# PG02_Full_Bridge.net
KiCad netlist of a schematic drawn in Altium Designer
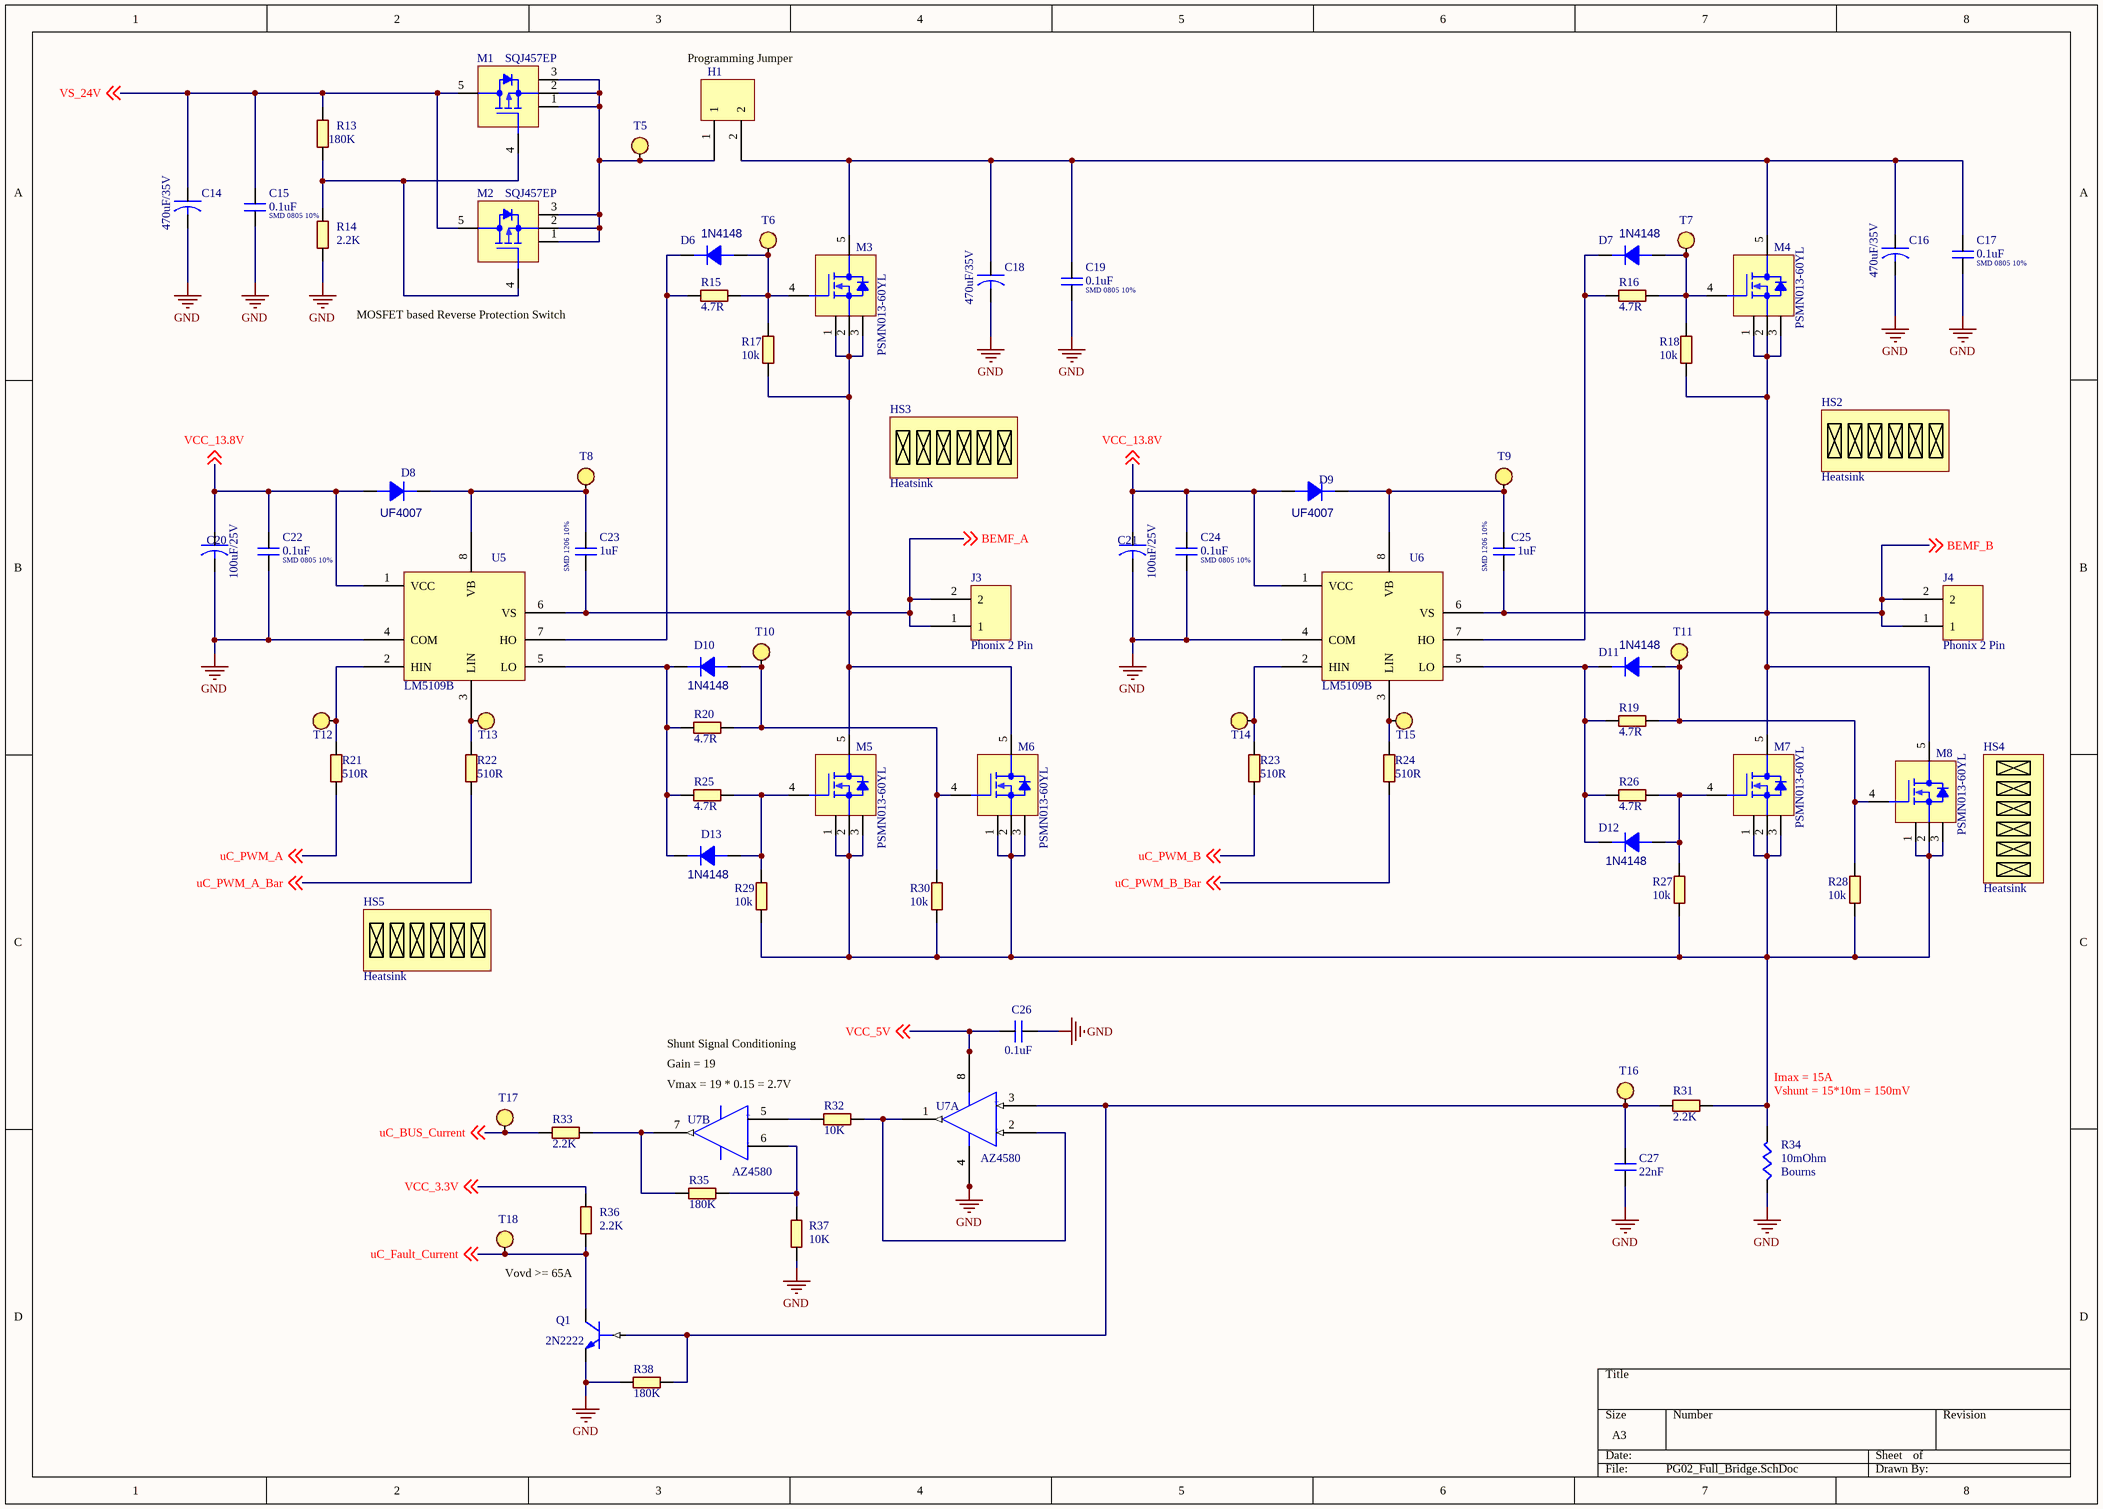
[diagram p0: PG02_Full_Bridge.SchDoc]

(export (version "E")
  (design (tool "Eeschema 10.0.6"))
  (components
    (comp (ref "C14")
      (value "470uF/35V")
      (fields (field (name "Comment") "Electrolyte Cap"))
      (libsource (lib "*") (part "CAP"))
    )
    (comp (ref "C15")
      (value "SMD 0805 10%")
      (footprint "SMD0805")
      (fields (field (name "MANUFACTURER") "Vishay") (field (name "ALTIUM_VALUE") "0.1uF"))
      (libsource (lib "Schlib1") (part "CAP_SMD"))
    )
    (comp (ref "C16")
      (value "470uF/35V")
      (fields (field (name "Comment") "Electrolyte Cap"))
      (libsource (lib "*") (part "CAP"))
    )
    (comp (ref "C17")
      (value "SMD 0805 10%")
      (footprint "SMD0805")
      (fields (field (name "MANUFACTURER") "Vishay") (field (name "ALTIUM_VALUE") "0.1uF"))
      (libsource (lib "Schlib1") (part "CAP_SMD"))
    )
    (comp (ref "C18")
      (value "470uF/35V")
      (fields (field (name "Comment") "Electrolyte Cap"))
      (libsource (lib "*") (part "CAP"))
    )
    (comp (ref "C19")
      (value "SMD 0805 10%")
      (footprint "SMD0805")
      (fields (field (name "MANUFACTURER") "Vishay") (field (name "ALTIUM_VALUE") "0.1uF"))
      (libsource (lib "Schlib1") (part "CAP_SMD"))
    )
    (comp (ref "C20") (value "100uF/25V") (footprint "CAP 5MM") (libsource (lib "*") (part "CAP")))
    (comp (ref "C21") (value "100uF/25V") (footprint "CAP 5MM") (libsource (lib "*") (part "CAP")))
    (comp (ref "C22")
      (value "SMD 0805 10%")
      (footprint "SMD0805")
      (fields (field (name "MANUFACTURER") "Vishay") (field (name "ALTIUM_VALUE") "0.1uF"))
      (libsource (lib "Schlib1") (part "CAP_SMD"))
    )
    (comp (ref "C23")
      (value "SMD 1206 10%")
      (footprint "SMD1206")
      (fields (field (name "MANUFACTURER") "Vishay") (field (name "ALTIUM_VALUE") "1uF"))
      (libsource (lib "Schlib1") (part "CAP_SMD"))
    )
    (comp (ref "C24")
      (value "SMD 0805 10%")
      (footprint "SMD0805")
      (fields (field (name "MANUFACTURER") "Vishay") (field (name "ALTIUM_VALUE") "0.1uF"))
      (libsource (lib "Schlib1") (part "CAP_SMD"))
    )
    (comp (ref "C25")
      (value "SMD 1206 10%")
      (footprint "SMD1206")
      (fields (field (name "MANUFACTURER") "Vishay") (field (name "ALTIUM_VALUE") "1uF"))
      (libsource (lib "Schlib1") (part "CAP_SMD"))
    )
    (comp (ref "C26")
      (value "0.1uF")
      (footprint "SMD0805")
      (fields (field (name "MANUFACTURER") "Vishay") (field (name "Comment") "SMD 0805 10%"))
      (libsource (lib "Schlib1") (part "CAP_SMD"))
    )
    (comp (ref "C27")
      (value "22nF")
      (footprint "SMD0805")
      (fields (field (name "MANUFACTURER") "Vishay") (field (name "Comment") "SMD 0805 10%"))
      (libsource (lib "Schlib1") (part "CAP_SMD"))
    )
    (comp (ref "D6")
      (value "1N4148")
      (fields
        (field (name "PART NO.") "SM4007")
        (field (name "TOLERANCE") "10%")
        (field (name "MANUFACTURER") "Vishay")
      )
      (libsource (lib "*") (part "1N4148"))
    )
    (comp (ref "D7")
      (value "1N4148")
      (fields
        (field (name "PART NO.") "SM4007")
        (field (name "TOLERANCE") "10%")
        (field (name "MANUFACTURER") "Vishay")
      )
      (libsource (lib "*") (part "1N4148"))
    )
    (comp (ref "D8")
      (value "UF4007")
      (fields
        (field (name "PART NO.") "SM4007")
        (field (name "TOLERANCE") "10%")
        (field (name "MANUFACTURER") "Vishay")
      )
      (libsource (lib "*") (part "1N4148"))
    )
    (comp (ref "D9")
      (value "UF4007")
      (fields
        (field (name "PART NO.") "SM4007")
        (field (name "TOLERANCE") "10%")
        (field (name "MANUFACTURER") "Vishay")
      )
      (libsource (lib "*") (part "1N4148"))
    )
    (comp (ref "D10")
      (value "1N4148")
      (fields
        (field (name "PART NO.") "SM4007")
        (field (name "TOLERANCE") "10%")
        (field (name "MANUFACTURER") "Vishay")
      )
      (libsource (lib "*") (part "1N4148"))
    )
    (comp (ref "D11")
      (value "1N4148")
      (fields
        (field (name "PART NO.") "SM4007")
        (field (name "TOLERANCE") "10%")
        (field (name "MANUFACTURER") "Vishay")
      )
      (libsource (lib "*") (part "1N4148"))
    )
    (comp (ref "D12")
      (value "1N4148")
      (fields
        (field (name "PART NO.") "SM4007")
        (field (name "TOLERANCE") "10%")
        (field (name "MANUFACTURER") "Vishay")
      )
      (libsource (lib "*") (part "1N4148"))
    )
    (comp (ref "D13")
      (value "1N4148")
      (fields
        (field (name "PART NO.") "SM4007")
        (field (name "TOLERANCE") "10%")
        (field (name "MANUFACTURER") "Vishay")
      )
      (libsource (lib "*") (part "1N4148"))
    )
    (comp (ref "H1")
      (value "Header 2 pin")
      (footprint "Header-2-Pin")
      (libsource (lib "Schlib1") (part "Header_2_Pin"))
    )
    (comp (ref "HS2") (value "Heatsink") (footprint "Heatsink_25mm") (libsource (lib "") (part "HS_15W_1")))
    (comp (ref "HS3") (value "Heatsink") (footprint "Heatsink_25mm") (libsource (lib "") (part "HS_15W_1")))
    (comp (ref "HS4")
      (value "Heatsink")
      (footprint "Heatsink_25mm")
      (libsource (lib "Schlib1") (part "HS_15W"))
    )
    (comp (ref "HS5") (value "Heatsink") (footprint "Heatsink_25mm") (libsource (lib "") (part "HS_15W_1")))
    (comp (ref "J3")
      (value "Phonix 2 Pin")
      (footprint "PHONIX2")
      (libsource (lib "Schlib1") (part "Phonix_2_Pin"))
    )
    (comp (ref "J4")
      (value "Phonix 2 Pin")
      (footprint "PHONIX2")
      (libsource (lib "Schlib1") (part "Phonix_2_Pin"))
    )
    (comp (ref "M1")
      (value "SQJ457EP")
      (footprint "SO8-L")
      (fields (field (name "MANUFACTURER") "Vishay") (field (name "Comment") "P MOSFET"))
      (libsource (lib "Schlib1") (part "PMOS_SQJ457EP"))
    )
    (comp (ref "M2")
      (value "SQJ457EP")
      (footprint "SO8-L")
      (fields (field (name "MANUFACTURER") "Vishay") (field (name "Comment") "P MOSFET"))
      (libsource (lib "Schlib1") (part "PMOS_SQJ457EP"))
    )
    (comp (ref "M3")
      (value "PSMN013-60YL")
      (footprint "SO8-L")
      (fields (field (name "MANUFACTURER") "NxP") (field (name "Comment") "N MOSFET"))
      (libsource (lib "Schlib1") (part "MOS_PSMN013-60YL"))
    )
    (comp (ref "M4")
      (value "PSMN013-60YL")
      (footprint "SO8-L")
      (fields (field (name "MANUFACTURER") "NxP") (field (name "Comment") "N MOSFET"))
      (libsource (lib "Schlib1") (part "MOS_PSMN013-60YL"))
    )
    (comp (ref "M5")
      (value "PSMN013-60YL")
      (footprint "SO8-L")
      (fields (field (name "MANUFACTURER") "NxP") (field (name "Comment") "N MOSFET"))
      (libsource (lib "Schlib1") (part "MOS_PSMN013-60YL"))
    )
    (comp (ref "M6")
      (value "PSMN013-60YL")
      (footprint "SO8-L")
      (fields (field (name "MANUFACTURER") "NxP") (field (name "Comment") "N MOSFET"))
      (libsource (lib "Schlib1") (part "MOS_PSMN013-60YL"))
    )
    (comp (ref "M7")
      (value "PSMN013-60YL")
      (footprint "SO8-L")
      (fields (field (name "MANUFACTURER") "NxP") (field (name "Comment") "N MOSFET"))
      (libsource (lib "Schlib1") (part "MOS_PSMN013-60YL"))
    )
    (comp (ref "M8")
      (value "PSMN013-60YL")
      (footprint "SO8-L")
      (fields (field (name "MANUFACTURER") "NxP") (field (name "Comment") "N MOSFET"))
      (libsource (lib "Schlib1") (part "MOS_PSMN013-60YL"))
    )
    (comp (ref "Q1")
      (value "2N2222")
      (fields (field (name "MANUFACTURER") "OnSemi") (field (name "Comment") "NPN Transistor"))
      (libsource (lib "*") (part "2N3904_1"))
    )
    (comp (ref "R13")
      (value "180K")
      (footprint "SMD1206")
      (description "SMD1206  1% Resistor")
      (fields (field (name "MANUFACTURER") "Vishay") (field (name "Comment") "SMD 1206 1%"))
      (libsource (lib "") (part "RES_SMD_1"))
    )
    (comp (ref "R14")
      (value "2.2K")
      (footprint "SMD1206")
      (description "SMD1206  1% Resistor")
      (fields (field (name "MANUFACTURER") "Vishay") (field (name "Comment") "SMD 1206 1%"))
      (libsource (lib "") (part "RES_SMD_1"))
    )
    (comp (ref "R15")
      (value "4.7R")
      (footprint "SMD1206")
      (description "SMD1206  1% Resistor")
      (fields (field (name "MANUFACTURER") "Vishay") (field (name "Comment") "SMD 1206 1%"))
      (libsource (lib "") (part "RES_SMD_2"))
    )
    (comp (ref "R16")
      (value "4.7R")
      (footprint "SMD1206")
      (description "SMD1206  1% Resistor")
      (fields (field (name "MANUFACTURER") "Vishay") (field (name "Comment") "SMD 1206 1%"))
      (libsource (lib "") (part "RES_SMD_2"))
    )
    (comp (ref "R17")
      (value "10k")
      (footprint "SMD1206")
      (description "SMD1206  1% Resistor")
      (fields (field (name "MANUFACTURER") "Vishay") (field (name "Comment") "SMD 1206 1%"))
      (libsource (lib "") (part "RES_SMD_3"))
    )
    (comp (ref "R18")
      (value "10k")
      (footprint "SMD1206")
      (description "SMD1206  1% Resistor")
      (fields (field (name "MANUFACTURER") "Vishay") (field (name "Comment") "SMD 1206 1%"))
      (libsource (lib "") (part "RES_SMD_3"))
    )
    (comp (ref "R19")
      (value "4.7R")
      (footprint "SMD1206")
      (description "SMD1206  1% Resistor")
      (fields (field (name "MANUFACTURER") "Vishay") (field (name "Comment") "SMD 1206 1%"))
      (libsource (lib "") (part "RES_SMD_2"))
    )
    (comp (ref "R20")
      (value "4.7R")
      (footprint "SMD1206")
      (description "SMD1206  1% Resistor")
      (fields (field (name "MANUFACTURER") "Vishay") (field (name "Comment") "SMD 1206 1%"))
      (libsource (lib "Schlib1") (part "RES_SMD"))
    )
    (comp (ref "R21")
      (value "510R")
      (footprint "SMD1206")
      (description "SMD1206  1% Resistor")
      (fields (field (name "MANUFACTURER") "Vishay") (field (name "Comment") "SMD 1206 1%"))
      (libsource (lib "") (part "RES_SMD_1"))
    )
    (comp (ref "R22")
      (value "510R")
      (footprint "SMD1206")
      (description "SMD1206  1% Resistor")
      (fields (field (name "MANUFACTURER") "Vishay") (field (name "Comment") "SMD 1206 1%"))
      (libsource (lib "") (part "RES_SMD_1"))
    )
    (comp (ref "R23")
      (value "510R")
      (footprint "SMD1206")
      (description "SMD1206  1% Resistor")
      (fields (field (name "MANUFACTURER") "Vishay") (field (name "Comment") "SMD 1206 1%"))
      (libsource (lib "") (part "RES_SMD_1"))
    )
    (comp (ref "R24")
      (value "510R")
      (footprint "SMD1206")
      (description "SMD1206  1% Resistor")
      (fields (field (name "MANUFACTURER") "Vishay") (field (name "Comment") "SMD 1206 1%"))
      (libsource (lib "") (part "RES_SMD_1"))
    )
    (comp (ref "R25")
      (value "4.7R")
      (footprint "SMD1206")
      (description "SMD1206  1% Resistor")
      (fields (field (name "MANUFACTURER") "Vishay") (field (name "Comment") "SMD 1206 1%"))
      (libsource (lib "") (part "RES_SMD_2"))
    )
    (comp (ref "R26")
      (value "4.7R")
      (footprint "SMD1206")
      (description "SMD1206  1% Resistor")
      (fields (field (name "MANUFACTURER") "Vishay") (field (name "Comment") "SMD 1206 1%"))
      (libsource (lib "") (part "RES_SMD_2"))
    )
    (comp (ref "R27")
      (value "10k")
      (footprint "SMD1206")
      (description "SMD1206  1% Resistor")
      (fields (field (name "MANUFACTURER") "Vishay") (field (name "Comment") "SMD 1206 1%"))
      (libsource (lib "") (part "RES_SMD_3"))
    )
    (comp (ref "R28")
      (value "10k")
      (footprint "SMD1206")
      (description "SMD1206  1% Resistor")
      (fields (field (name "MANUFACTURER") "Vishay") (field (name "Comment") "SMD 1206 1%"))
      (libsource (lib "") (part "RES_SMD_3"))
    )
    (comp (ref "R29")
      (value "10k")
      (footprint "SMD1206")
      (description "SMD1206  1% Resistor")
      (fields (field (name "MANUFACTURER") "Vishay") (field (name "Comment") "SMD 1206 1%"))
      (libsource (lib "") (part "RES_SMD_3"))
    )
    (comp (ref "R30")
      (value "10k")
      (footprint "SMD1206")
      (description "SMD1206  1% Resistor")
      (fields (field (name "MANUFACTURER") "Vishay") (field (name "Comment") "SMD 1206 1%"))
      (libsource (lib "") (part "RES_SMD_3"))
    )
    (comp (ref "R31")
      (value "2.2K")
      (footprint "SMD1206")
      (description "SMD1206  1% Resistor")
      (fields (field (name "MANUFACTURER") "Vishay") (field (name "Comment") "SMD 1206 1%"))
      (libsource (lib "Schlib1") (part "RES_SMD"))
    )
    (comp (ref "R32")
      (value "10K")
      (footprint "SMD1206")
      (description "SMD1206  1% Resistor")
      (fields (field (name "MANUFACTURER") "Vishay") (field (name "Comment") "SMD 1206 1%"))
      (libsource (lib "Schlib1") (part "RES_SMD"))
    )
    (comp (ref "R33")
      (value "2.2K")
      (footprint "SMD1206")
      (description "SMD1206  1% Resistor")
      (fields (field (name "MANUFACTURER") "Vishay") (field (name "Comment") "SMD 1206 1%"))
      (libsource (lib "Schlib1") (part "RES_SMD"))
    )
    (comp (ref "R34")
      (value "10mOhm")
      (footprint "SMD2512")
      (fields (field (name "MANUFACTURER") "Bourns") (field (name "Comment") "CRA2512"))
      (libsource (lib "Schlib1") (part "RES_TH"))
    )
    (comp (ref "R35")
      (value "180K")
      (footprint "SMD1206")
      (description "SMD1206  1% Resistor")
      (fields (field (name "MANUFACTURER") "Vishay") (field (name "Comment") "SMD 1206 1%"))
      (libsource (lib "Schlib1") (part "RES_SMD"))
    )
    (comp (ref "R36")
      (value "2.2K")
      (footprint "SMD1206")
      (description "SMD1206  1% Resistor")
      (fields (field (name "MANUFACTURER") "Vishay") (field (name "Comment") "SMD 1206 1%"))
      (libsource (lib "") (part "RES_SMD_3"))
    )
    (comp (ref "R37")
      (value "10K")
      (footprint "SMD1206")
      (description "SMD1206  1% Resistor")
      (fields (field (name "MANUFACTURER") "Vishay") (field (name "Comment") "SMD 1206 1%"))
      (libsource (lib "") (part "RES_SMD_3"))
    )
    (comp (ref "R38")
      (value "180K")
      (footprint "SMD1206")
      (description "SMD1206  1% Resistor")
      (fields (field (name "MANUFACTURER") "Vishay") (field (name "Comment") "SMD 1206 1%"))
      (libsource (lib "Schlib1") (part "RES_SMD"))
    )
    (comp (ref "T5")
      (value "Through hole TestPoint")
      (footprint "TP")
      (libsource (lib "Schlib1") (part "TestPoint_TH"))
    )
    (comp (ref "T6")
      (value "Through hole TestPoint")
      (footprint "TP")
      (libsource (lib "Schlib1") (part "TestPoint_TH"))
    )
    (comp (ref "T7")
      (value "Through hole TestPoint")
      (footprint "TP")
      (libsource (lib "Schlib1") (part "TestPoint_TH"))
    )
    (comp (ref "T8")
      (value "Through hole TestPoint")
      (footprint "TP")
      (libsource (lib "Schlib1") (part "TestPoint_TH"))
    )
    (comp (ref "T9")
      (value "Through hole TestPoint")
      (footprint "TP")
      (libsource (lib "Schlib1") (part "TestPoint_TH"))
    )
    (comp (ref "T10")
      (value "Through hole TestPoint")
      (footprint "TP")
      (libsource (lib "Schlib1") (part "TestPoint_TH"))
    )
    (comp (ref "T11")
      (value "Through hole TestPoint")
      (footprint "TP")
      (libsource (lib "Schlib1") (part "TestPoint_TH"))
    )
    (comp (ref "T12")
      (value "Through hole TestPoint")
      (footprint "TP")
      (libsource (lib "") (part "TestPoint_TH_2"))
    )
    (comp (ref "T13")
      (value "Through hole TestPoint")
      (footprint "TP")
      (libsource (lib "") (part "TestPoint_TH_1"))
    )
    (comp (ref "T14")
      (value "Through hole TestPoint")
      (footprint "TP")
      (libsource (lib "") (part "TestPoint_TH_2"))
    )
    (comp (ref "T15")
      (value "Through hole TestPoint")
      (footprint "TP")
      (libsource (lib "") (part "TestPoint_TH_1"))
    )
    (comp (ref "T16")
      (value "Through hole TestPoint")
      (footprint "TP")
      (libsource (lib "Schlib1") (part "TestPoint_TH"))
    )
    (comp (ref "T17")
      (value "Through hole TestPoint")
      (footprint "TP")
      (libsource (lib "Schlib1") (part "TestPoint_TH"))
    )
    (comp (ref "T18")
      (value "Through hole TestPoint")
      (footprint "TP")
      (libsource (lib "Schlib1") (part "TestPoint_TH"))
    )
    (comp (ref "U5") (value "LM5109B") (footprint "SOIC-8") (libsource (lib "Schlib1") (part "IR2106")))
    (comp (ref "U6") (value "LM5109B") (footprint "SOIC-8") (libsource (lib "Schlib1") (part "IR2106")))
    (comp (ref "U7")
      (value "AZ4580")
      (footprint "SOIC-8")
      (fields (field (name "MANUFACTURER") "ST Semiconductor") (field (name "Comment") "LM358"))
      (libsource (lib "*") (part "LM358"))
    )
  )
  (nets
    (net (code "1") (name "BEMF_A") (class "Default")
      (node (ref "C23") (pin "2") (pinfunction "2_2") (pintype "passive"))
      (node (ref "J3") (pin "1") (pinfunction "1_1") (pintype "passive"))
      (node (ref "J3") (pin "2") (pinfunction "2_2") (pintype "passive"))
      (node (ref "M3") (pin "1") (pinfunction "1_1") (pintype "passive"))
      (node (ref "M3") (pin "2") (pinfunction "2_2") (pintype "passive"))
      (node (ref "M3") (pin "3") (pinfunction "3_3") (pintype "passive"))
      (node (ref "M5") (pin "5") (pinfunction "5_5") (pintype "passive"))
      (node (ref "M6") (pin "5") (pinfunction "5_5") (pintype "passive"))
      (node (ref "R17") (pin "1") (pinfunction "1_1") (pintype "passive"))
      (node (ref "U5") (pin "6") (pinfunction "VS_6") (pintype "passive"))
    )
    (net (code "2") (name "BEMF_B") (class "Default")
      (node (ref "C25") (pin "2") (pinfunction "2_2") (pintype "passive"))
      (node (ref "J4") (pin "1") (pinfunction "1_1") (pintype "passive"))
      (node (ref "J4") (pin "2") (pinfunction "2_2") (pintype "passive"))
      (node (ref "M4") (pin "1") (pinfunction "1_1") (pintype "passive"))
      (node (ref "M4") (pin "2") (pinfunction "2_2") (pintype "passive"))
      (node (ref "M4") (pin "3") (pinfunction "3_3") (pintype "passive"))
      (node (ref "M7") (pin "5") (pinfunction "5_5") (pintype "passive"))
      (node (ref "M8") (pin "5") (pinfunction "5_5") (pintype "passive"))
      (node (ref "R18") (pin "1") (pinfunction "1_1") (pintype "passive"))
      (node (ref "U6") (pin "6") (pinfunction "VS_6") (pintype "passive"))
    )
    (net (code "3") (name "GND") (class "Default")
      (node (ref "C14") (pin "2") (pinfunction "2_2") (pintype "passive"))
      (node (ref "C15") (pin "2") (pinfunction "2_2") (pintype "passive"))
      (node (ref "C16") (pin "2") (pinfunction "2_2") (pintype "passive"))
      (node (ref "C17") (pin "2") (pinfunction "2_2") (pintype "passive"))
      (node (ref "C18") (pin "2") (pinfunction "2_2") (pintype "passive"))
      (node (ref "C19") (pin "2") (pinfunction "2_2") (pintype "passive"))
      (node (ref "C20") (pin "2") (pinfunction "2_2") (pintype "passive"))
      (node (ref "C21") (pin "2") (pinfunction "2_2") (pintype "passive"))
      (node (ref "C22") (pin "2") (pinfunction "2_2") (pintype "passive"))
      (node (ref "C24") (pin "2") (pinfunction "2_2") (pintype "passive"))
      (node (ref "C26") (pin "2") (pinfunction "2_2") (pintype "passive"))
      (node (ref "C27") (pin "2") (pinfunction "2_2") (pintype "passive"))
      (node (ref "Q1") (pin "2") (pinfunction "EMITTER_2") (pintype "passive"))
      (node (ref "R14") (pin "2") (pinfunction "2_2") (pintype "passive"))
      (node (ref "R34") (pin "1") (pintype "passive"))
      (node (ref "R37") (pin "1") (pinfunction "1_1") (pintype "passive"))
      (node (ref "R38") (pin "1") (pinfunction "1_1") (pintype "passive"))
      (node (ref "U5") (pin "4") (pinfunction "COM_4") (pintype "passive"))
      (node (ref "U6") (pin "4") (pinfunction "COM_4") (pintype "passive"))
      (node (ref "U7") (pin "4") (pinfunction "GND_4") (pintype "power_in"))
    )
    (net (code "4") (name "Net-(C16-Pad1)") (class "Default")
      (node (ref "C16") (pin "1") (pinfunction "1_1") (pintype "passive"))
      (node (ref "C17") (pin "1") (pinfunction "1_1") (pintype "passive"))
      (node (ref "C18") (pin "1") (pinfunction "1_1") (pintype "passive"))
      (node (ref "C19") (pin "1") (pinfunction "1_1") (pintype "passive"))
      (node (ref "H1") (pin "2") (pinfunction "2_2") (pintype "passive"))
      (node (ref "M3") (pin "5") (pinfunction "5_5") (pintype "passive"))
      (node (ref "M4") (pin "5") (pinfunction "5_5") (pintype "passive"))
    )
    (net (code "5") (name "Net-(D6-ANODE)") (class "Default")
      (node (ref "D6") (pin "1") (pinfunction "ANODE_1") (pintype "passive"))
      (node (ref "M3") (pin "4") (pinfunction "G_4") (pintype "passive"))
      (node (ref "R15") (pin "1") (pinfunction "1_1") (pintype "passive"))
      (node (ref "R17") (pin "2") (pinfunction "2_2") (pintype "passive"))
      (node (ref "T6") (pin "1") (pintype "passive"))
    )
    (net (code "6") (name "Net-(D6-CATHODE)") (class "Default")
      (node (ref "D6") (pin "2") (pinfunction "CATHODE_2") (pintype "passive"))
      (node (ref "R15") (pin "2") (pinfunction "2_2") (pintype "passive"))
      (node (ref "U5") (pin "7") (pinfunction "HO_7") (pintype "passive"))
    )
    (net (code "7") (name "Net-(D7-ANODE)") (class "Default")
      (node (ref "D7") (pin "1") (pinfunction "ANODE_1") (pintype "passive"))
      (node (ref "M4") (pin "4") (pinfunction "G_4") (pintype "passive"))
      (node (ref "R16") (pin "1") (pinfunction "1_1") (pintype "passive"))
      (node (ref "R18") (pin "2") (pinfunction "2_2") (pintype "passive"))
      (node (ref "T7") (pin "1") (pintype "passive"))
    )
    (net (code "8") (name "Net-(D7-CATHODE)") (class "Default")
      (node (ref "D7") (pin "2") (pinfunction "CATHODE_2") (pintype "passive"))
      (node (ref "R16") (pin "2") (pinfunction "2_2") (pintype "passive"))
      (node (ref "U6") (pin "7") (pinfunction "HO_7") (pintype "passive"))
    )
    (net (code "9") (name "Net-(D8-CATHODE)") (class "Default")
      (node (ref "C23") (pin "1") (pinfunction "1_1") (pintype "passive"))
      (node (ref "D8") (pin "2") (pinfunction "CATHODE_2") (pintype "passive"))
      (node (ref "T8") (pin "1") (pintype "passive"))
      (node (ref "U5") (pin "8") (pinfunction "VB_8") (pintype "passive"))
    )
    (net (code "10") (name "Net-(D9-CATHODE)") (class "Default")
      (node (ref "C25") (pin "1") (pinfunction "1_1") (pintype "passive"))
      (node (ref "D9") (pin "2") (pinfunction "CATHODE_2") (pintype "passive"))
      (node (ref "T9") (pin "1") (pintype "passive"))
      (node (ref "U6") (pin "8") (pinfunction "VB_8") (pintype "passive"))
    )
    (net (code "11") (name "Net-(D10-ANODE)") (class "Default")
      (node (ref "D10") (pin "1") (pinfunction "ANODE_1") (pintype "passive"))
      (node (ref "M6") (pin "4") (pinfunction "G_4") (pintype "passive"))
      (node (ref "R20") (pin "2") (pinfunction "2_2") (pintype "passive"))
      (node (ref "R30") (pin "2") (pinfunction "2_2") (pintype "passive"))
      (node (ref "T10") (pin "1") (pintype "passive"))
    )
    (net (code "12") (name "Net-(D10-CATHODE)") (class "Default")
      (node (ref "D10") (pin "2") (pinfunction "CATHODE_2") (pintype "passive"))
      (node (ref "D13") (pin "2") (pinfunction "CATHODE_2") (pintype "passive"))
      (node (ref "R20") (pin "1") (pinfunction "1_1") (pintype "passive"))
      (node (ref "R25") (pin "2") (pinfunction "2_2") (pintype "passive"))
      (node (ref "U5") (pin "5") (pinfunction "LO_5") (pintype "passive"))
    )
    (net (code "13") (name "Net-(D11-ANODE)") (class "Default")
      (node (ref "D11") (pin "1") (pinfunction "ANODE_1") (pintype "passive"))
      (node (ref "M8") (pin "4") (pinfunction "G_4") (pintype "passive"))
      (node (ref "R19") (pin "1") (pinfunction "1_1") (pintype "passive"))
      (node (ref "R28") (pin "2") (pinfunction "2_2") (pintype "passive"))
      (node (ref "T11") (pin "1") (pintype "passive"))
    )
    (net (code "14") (name "Net-(D11-CATHODE)") (class "Default")
      (node (ref "D11") (pin "2") (pinfunction "CATHODE_2") (pintype "passive"))
      (node (ref "D12") (pin "2") (pinfunction "CATHODE_2") (pintype "passive"))
      (node (ref "R19") (pin "2") (pinfunction "2_2") (pintype "passive"))
      (node (ref "R26") (pin "2") (pinfunction "2_2") (pintype "passive"))
      (node (ref "U6") (pin "5") (pinfunction "LO_5") (pintype "passive"))
    )
    (net (code "15") (name "Net-(D12-ANODE)") (class "Default")
      (node (ref "D12") (pin "1") (pinfunction "ANODE_1") (pintype "passive"))
      (node (ref "M7") (pin "4") (pinfunction "G_4") (pintype "passive"))
      (node (ref "R26") (pin "1") (pinfunction "1_1") (pintype "passive"))
      (node (ref "R27") (pin "2") (pinfunction "2_2") (pintype "passive"))
    )
    (net (code "16") (name "Net-(D13-ANODE)") (class "Default")
      (node (ref "D13") (pin "1") (pinfunction "ANODE_1") (pintype "passive"))
      (node (ref "M5") (pin "4") (pinfunction "G_4") (pintype "passive"))
      (node (ref "R25") (pin "1") (pinfunction "1_1") (pintype "passive"))
      (node (ref "R29") (pin "2") (pinfunction "2_2") (pintype "passive"))
    )
    (net (code "17") (name "Net-(H1-Pad1)") (class "Default")
      (node (ref "H1") (pin "1") (pinfunction "1_1") (pintype "passive"))
      (node (ref "M1") (pin "1") (pinfunction "1_1") (pintype "passive"))
      (node (ref "M1") (pin "2") (pinfunction "2_2") (pintype "passive"))
      (node (ref "M1") (pin "3") (pinfunction "3_3") (pintype "passive"))
      (node (ref "M2") (pin "1") (pinfunction "1_1") (pintype "passive"))
      (node (ref "M2") (pin "2") (pinfunction "2_2") (pintype "passive"))
      (node (ref "M2") (pin "3") (pinfunction "3_3") (pintype "passive"))
      (node (ref "T5") (pin "1") (pintype "passive"))
    )
    (net (code "18") (name "Net-(M1-G)") (class "Default")
      (node (ref "M1") (pin "4") (pinfunction "G_4") (pintype "passive"))
      (node (ref "M2") (pin "4") (pinfunction "G_4") (pintype "passive"))
      (node (ref "R13") (pin "2") (pinfunction "2_2") (pintype "passive"))
      (node (ref "R14") (pin "1") (pinfunction "1_1") (pintype "passive"))
    )
    (net (code "19") (name "Net-(M5-Pad1)") (class "Default")
      (node (ref "M5") (pin "1") (pinfunction "1_1") (pintype "passive"))
      (node (ref "M5") (pin "2") (pinfunction "2_2") (pintype "passive"))
      (node (ref "M5") (pin "3") (pinfunction "3_3") (pintype "passive"))
      (node (ref "M6") (pin "1") (pinfunction "1_1") (pintype "passive"))
      (node (ref "M6") (pin "2") (pinfunction "2_2") (pintype "passive"))
      (node (ref "M6") (pin "3") (pinfunction "3_3") (pintype "passive"))
      (node (ref "M7") (pin "1") (pinfunction "1_1") (pintype "passive"))
      (node (ref "M7") (pin "2") (pinfunction "2_2") (pintype "passive"))
      (node (ref "M7") (pin "3") (pinfunction "3_3") (pintype "passive"))
      (node (ref "M8") (pin "1") (pinfunction "1_1") (pintype "passive"))
      (node (ref "M8") (pin "2") (pinfunction "2_2") (pintype "passive"))
      (node (ref "M8") (pin "3") (pinfunction "3_3") (pintype "passive"))
      (node (ref "R27") (pin "1") (pinfunction "1_1") (pintype "passive"))
      (node (ref "R28") (pin "1") (pinfunction "1_1") (pintype "passive"))
      (node (ref "R29") (pin "1") (pinfunction "1_1") (pintype "passive"))
      (node (ref "R30") (pin "1") (pinfunction "1_1") (pintype "passive"))
      (node (ref "R31") (pin "2") (pinfunction "2_2") (pintype "passive"))
      (node (ref "R34") (pin "2") (pintype "passive"))
    )
    (net (code "20") (name "Net-(Q1-BASE)") (class "Default")
      (node (ref "C27") (pin "1") (pinfunction "1_1") (pintype "passive"))
      (node (ref "Q1") (pin "1") (pinfunction "BASE_1") (pintype "input"))
      (node (ref "R31") (pin "1") (pinfunction "1_1") (pintype "passive"))
      (node (ref "R38") (pin "2") (pinfunction "2_2") (pintype "passive"))
      (node (ref "T16") (pin "1") (pintype "passive"))
      (node (ref "U7") (pin "3") (pinfunction "+IN_3") (pintype "input"))
    )
    (net (code "21") (name "Net-(U5-HIN)") (class "Default")
      (node (ref "R21") (pin "1") (pinfunction "1_1") (pintype "passive"))
      (node (ref "T12") (pin "1") (pintype "passive"))
      (node (ref "U5") (pin "2") (pinfunction "HIN_2") (pintype "passive"))
    )
    (net (code "22") (name "Net-(U5-LIN)") (class "Default")
      (node (ref "R22") (pin "1") (pinfunction "1_1") (pintype "passive"))
      (node (ref "T13") (pin "1") (pintype "passive"))
      (node (ref "U5") (pin "3") (pinfunction "LIN_3") (pintype "passive"))
    )
    (net (code "23") (name "Net-(U6-HIN)") (class "Default")
      (node (ref "R23") (pin "1") (pinfunction "1_1") (pintype "passive"))
      (node (ref "T14") (pin "1") (pintype "passive"))
      (node (ref "U6") (pin "2") (pinfunction "HIN_2") (pintype "passive"))
    )
    (net (code "24") (name "Net-(U6-LIN)") (class "Default")
      (node (ref "R24") (pin "1") (pinfunction "1_1") (pintype "passive"))
      (node (ref "T15") (pin "1") (pintype "passive"))
      (node (ref "U6") (pin "3") (pinfunction "LIN_3") (pintype "passive"))
    )
    (net (code "25") (name "Net-(U7A--IN)") (class "Default")
      (node (ref "R32") (pin "2") (pinfunction "2_2") (pintype "passive"))
      (node (ref "U7") (pin "1") (pinfunction "OUT_1") (pintype "output"))
      (node (ref "U7") (pin "2") (pinfunction "-IN_2") (pintype "input"))
    )
    (net (code "26") (name "Net-(U7B-+IN)") (class "Default")
      (node (ref "R32") (pin "1") (pinfunction "1_1") (pintype "passive"))
      (node (ref "U7") (pin "5") (pinfunction "+IN_5") (pintype "passive"))
    )
    (net (code "27") (name "Net-(U7B--IN)") (class "Default")
      (node (ref "R35") (pin "2") (pinfunction "2_2") (pintype "passive"))
      (node (ref "R37") (pin "2") (pinfunction "2_2") (pintype "passive"))
      (node (ref "U7") (pin "6") (pinfunction "-IN_6") (pintype "passive"))
    )
    (net (code "28") (name "Net-(U7B-OUT)") (class "Default")
      (node (ref "R33") (pin "2") (pinfunction "2_2") (pintype "passive"))
      (node (ref "R35") (pin "1") (pinfunction "1_1") (pintype "passive"))
      (node (ref "U7") (pin "7") (pinfunction "OUT_7") (pintype "output"))
    )
    (net (code "29") (name "VCC_3.3V") (class "Default")
      (node (ref "R36") (pin "2") (pinfunction "2_2") (pintype "passive"))
    )
    (net (code "30") (name "VCC_5V") (class "Default")
      (node (ref "C26") (pin "1") (pinfunction "1_1") (pintype "passive"))
      (node (ref "U7") (pin "8") (pinfunction "VCC_8") (pintype "power_in"))
    )
    (net (code "31") (name "VCC_13.8V") (class "Default")
      (node (ref "C20") (pin "1") (pinfunction "1_1") (pintype "passive"))
      (node (ref "C21") (pin "1") (pinfunction "1_1") (pintype "passive"))
      (node (ref "C22") (pin "1") (pinfunction "1_1") (pintype "passive"))
      (node (ref "C24") (pin "1") (pinfunction "1_1") (pintype "passive"))
      (node (ref "D8") (pin "1") (pinfunction "ANODE_1") (pintype "passive"))
      (node (ref "D9") (pin "1") (pinfunction "ANODE_1") (pintype "passive"))
      (node (ref "U5") (pin "1") (pinfunction "VCC_1") (pintype "passive"))
      (node (ref "U6") (pin "1") (pinfunction "VCC_1") (pintype "passive"))
    )
    (net (code "32") (name "VS_24V") (class "Default")
      (node (ref "C14") (pin "1") (pinfunction "1_1") (pintype "passive"))
      (node (ref "C15") (pin "1") (pinfunction "1_1") (pintype "passive"))
      (node (ref "M1") (pin "5") (pinfunction "5_5") (pintype "passive"))
      (node (ref "M2") (pin "5") (pinfunction "5_5") (pintype "passive"))
      (node (ref "R13") (pin "1") (pinfunction "1_1") (pintype "passive"))
    )
    (net (code "33") (name "uC_BUS_Current") (class "Default")
      (node (ref "R33") (pin "1") (pinfunction "1_1") (pintype "passive"))
      (node (ref "T17") (pin "1") (pintype "passive"))
    )
    (net (code "34") (name "uC_Fault_Current") (class "Default")
      (node (ref "Q1") (pin "3") (pinfunction "COLLECTOR_3") (pintype "passive"))
      (node (ref "R36") (pin "1") (pinfunction "1_1") (pintype "passive"))
      (node (ref "T18") (pin "1") (pintype "passive"))
    )
    (net (code "35") (name "uC_PWM_A") (class "Default")
      (node (ref "R21") (pin "2") (pinfunction "2_2") (pintype "passive"))
    )
    (net (code "36") (name "uC_PWM_A_Bar") (class "Default")
      (node (ref "R22") (pin "2") (pinfunction "2_2") (pintype "passive"))
    )
    (net (code "37") (name "uC_PWM_B") (class "Default")
      (node (ref "R23") (pin "2") (pinfunction "2_2") (pintype "passive"))
    )
    (net (code "38") (name "uC_PWM_B_Bar") (class "Default")
      (node (ref "R24") (pin "2") (pinfunction "2_2") (pintype "passive"))
    )
  )
)
